# EuroOwl.net
KiCad netlist of a schematic drawn in EAGLE
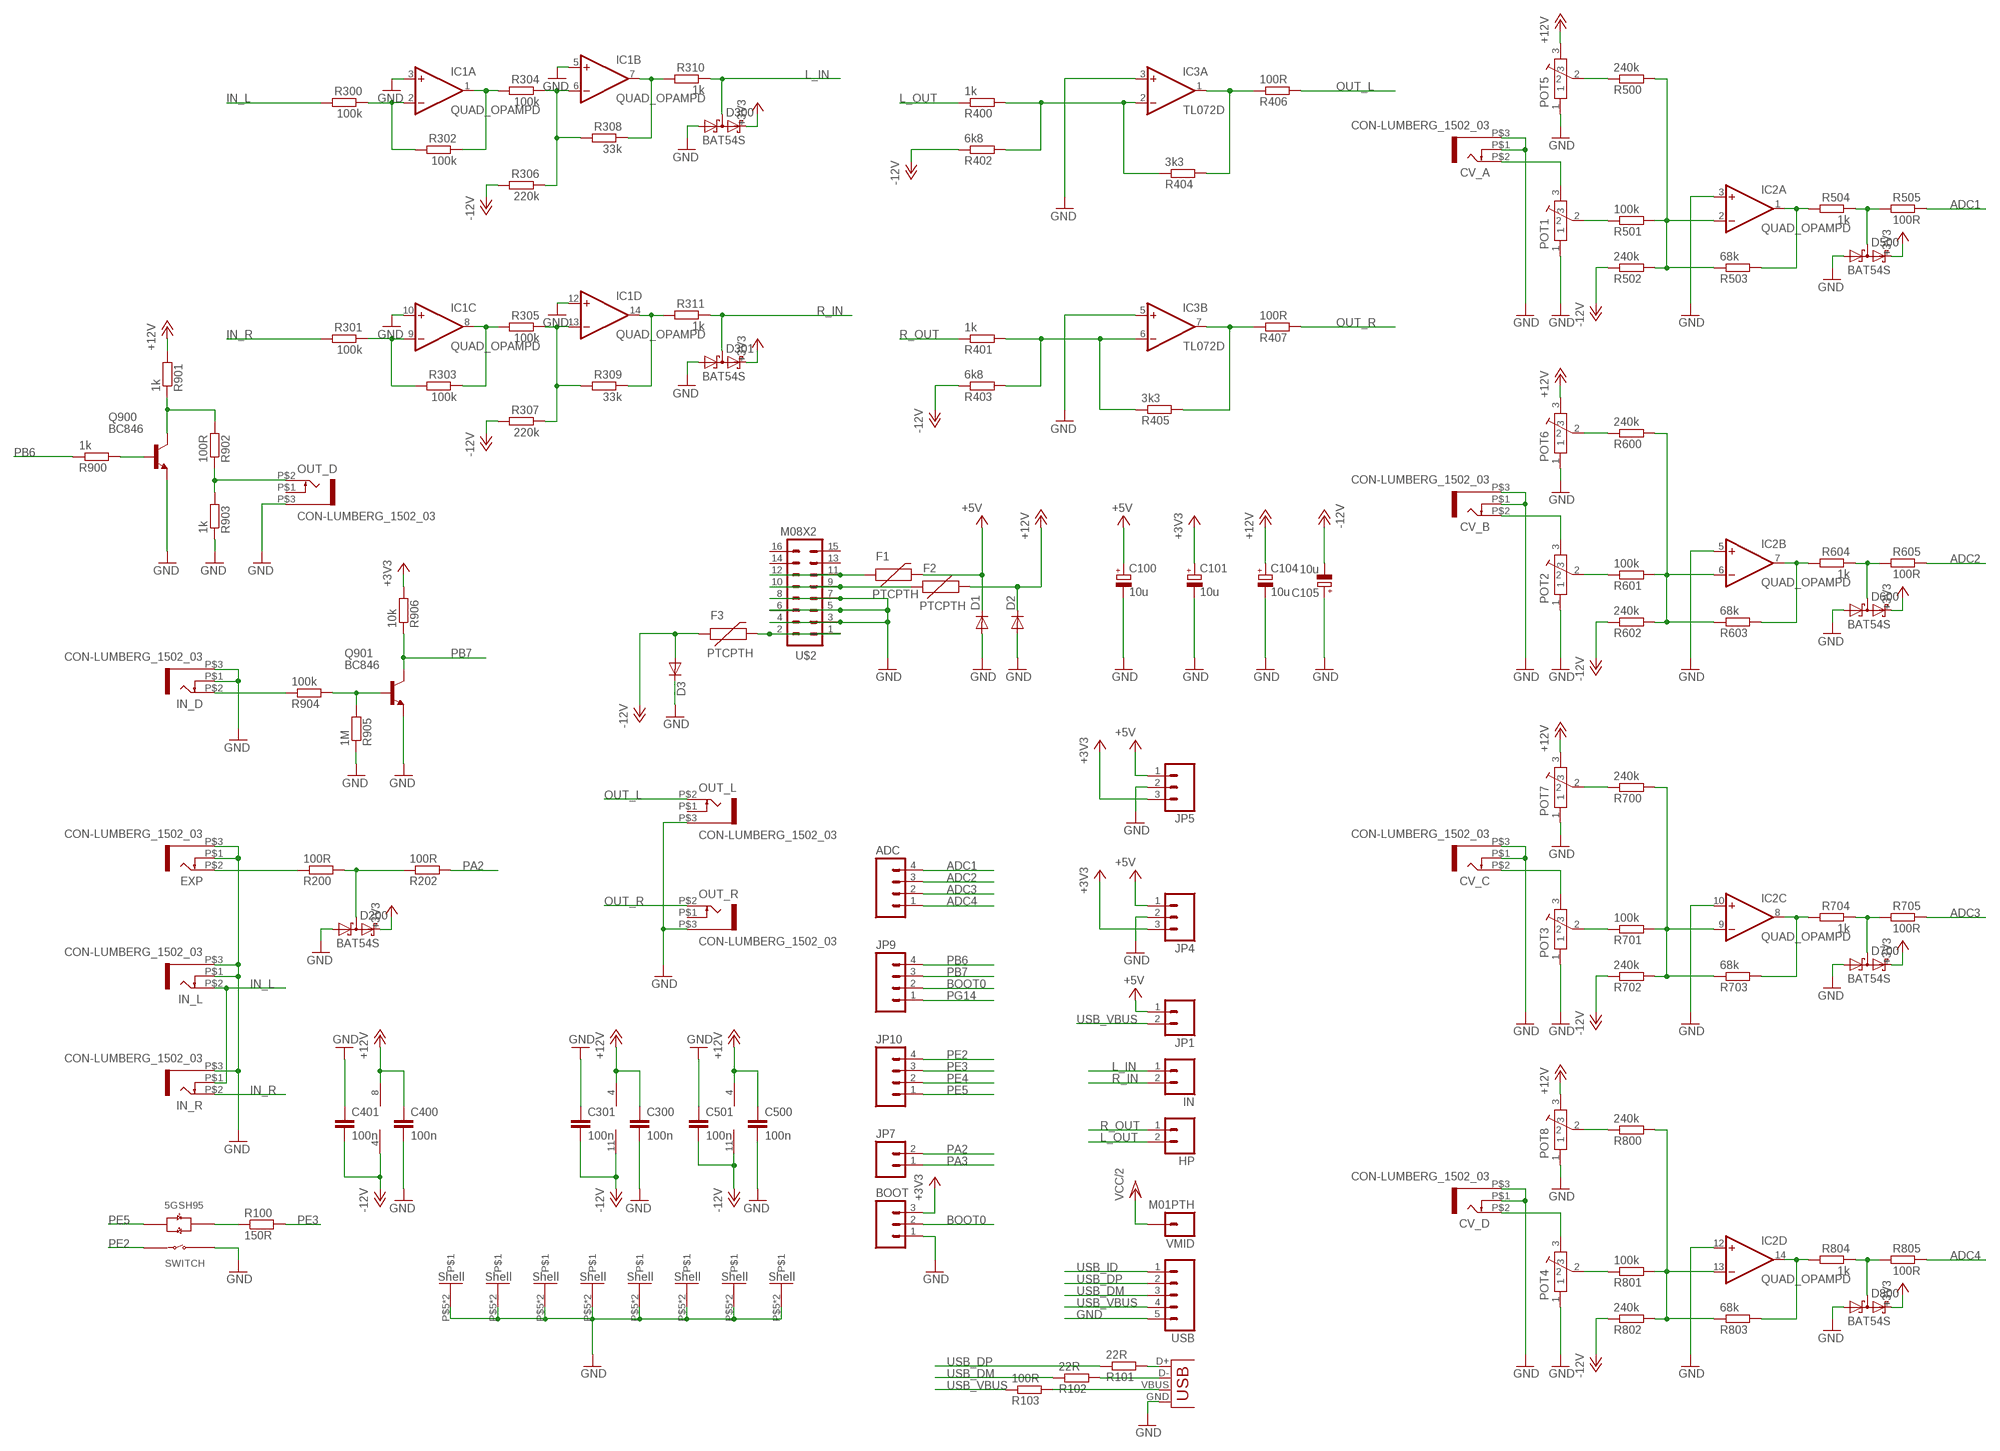
[diagram p0: schematic, sheet 1]

(export (version "E")
  (design (tool "Eeschema 10.0.6"))
  (components
    (comp (ref "ADC")
      (value "M04PTH")
      (footprint "eagle-import:1X04")
      (libsource (lib "eagle-import") (part "M04PTH"))
    )
    (comp (ref "BOOT")
      (value "M03PTH")
      (footprint "eagle-import:1X03")
      (libsource (lib "eagle-import") (part "M03PTH"))
    )
    (comp (ref "C100")
      (value "10u")
      (footprint "eagle-import:PANASONIC_A")
      (libsource (lib "eagle-import") (part "CPOL-EUA"))
    )
    (comp (ref "C101")
      (value "10u")
      (footprint "eagle-import:PANASONIC_A")
      (libsource (lib "eagle-import") (part "CPOL-EUA"))
    )
    (comp (ref "C104")
      (value "10u")
      (footprint "eagle-import:PANASONIC_A")
      (libsource (lib "eagle-import") (part "CPOL-EUA"))
    )
    (comp (ref "C105")
      (value "10u")
      (footprint "eagle-import:PANASONIC_A")
      (libsource (lib "eagle-import") (part "CPOL-EUA"))
    )
    (comp (ref "C300")
      (value "100n")
      (footprint "eagle-import:C0603")
      (libsource (lib "eagle-import") (part "C-EUC0603"))
    )
    (comp (ref "C301")
      (value "100n")
      (footprint "eagle-import:C0603")
      (libsource (lib "eagle-import") (part "C-EUC0603"))
    )
    (comp (ref "C400")
      (value "100n")
      (footprint "eagle-import:C0603")
      (libsource (lib "eagle-import") (part "C-EUC0603"))
    )
    (comp (ref "C401")
      (value "100n")
      (footprint "eagle-import:C0603")
      (libsource (lib "eagle-import") (part "C-EUC0603"))
    )
    (comp (ref "C500")
      (value "100n")
      (footprint "eagle-import:C0603")
      (libsource (lib "eagle-import") (part "C-EUC0603"))
    )
    (comp (ref "C501")
      (value "100n")
      (footprint "eagle-import:C0603")
      (libsource (lib "eagle-import") (part "C-EUC0603"))
    )
    (comp (ref "CV_A")
      (value "CON-LUMBERG_1502_03")
      (footprint "eagle-import:CON-LUMBERG_1502_03")
      (libsource (lib "eagle-import") (part "CON-LUMBERG_1502_03"))
    )
    (comp (ref "CV_B")
      (value "CON-LUMBERG_1502_03")
      (footprint "eagle-import:CON-LUMBERG_1502_03")
      (libsource (lib "eagle-import") (part "CON-LUMBERG_1502_03"))
    )
    (comp (ref "CV_C")
      (value "CON-LUMBERG_1502_03")
      (footprint "eagle-import:CON-LUMBERG_1502_03")
      (libsource (lib "eagle-import") (part "CON-LUMBERG_1502_03"))
    )
    (comp (ref "CV_D")
      (value "CON-LUMBERG_1502_03")
      (footprint "eagle-import:CON-LUMBERG_1502_03")
      (libsource (lib "eagle-import") (part "CON-LUMBERG_1502_03"))
    )
    (comp (ref "D1")
      (value "DIODE1N4001")
      (footprint "eagle-import:DIODE-1N4001")
      (libsource (lib "eagle-import") (part "DIODE1N4001"))
    )
    (comp (ref "D2")
      (value "DIODE1N4001")
      (footprint "eagle-import:DIODE-1N4001")
      (libsource (lib "eagle-import") (part "DIODE1N4001"))
    )
    (comp (ref "D3")
      (value "DIODE1N4001")
      (footprint "eagle-import:DIODE-1N4001")
      (libsource (lib "eagle-import") (part "DIODE1N4001"))
    )
    (comp (ref "D200")
      (value "BAT54S")
      (footprint "eagle-import:SOT23")
      (libsource (lib "eagle-import") (part "BAT54S"))
    )
    (comp (ref "D300")
      (value "BAT54S")
      (footprint "eagle-import:SOT23")
      (libsource (lib "eagle-import") (part "BAT54S"))
    )
    (comp (ref "D301")
      (value "BAT54S")
      (footprint "eagle-import:SOT23")
      (libsource (lib "eagle-import") (part "BAT54S"))
    )
    (comp (ref "D500")
      (value "BAT54S")
      (footprint "eagle-import:SOT23")
      (libsource (lib "eagle-import") (part "BAT54S"))
    )
    (comp (ref "D600")
      (value "BAT54S")
      (footprint "eagle-import:SOT23")
      (libsource (lib "eagle-import") (part "BAT54S"))
    )
    (comp (ref "D700")
      (value "BAT54S")
      (footprint "eagle-import:SOT23")
      (libsource (lib "eagle-import") (part "BAT54S"))
    )
    (comp (ref "D800")
      (value "BAT54S")
      (footprint "eagle-import:SOT23")
      (libsource (lib "eagle-import") (part "BAT54S"))
    )
    (comp (ref "EXP")
      (value "CON-LUMBERG_1502_03")
      (footprint "eagle-import:CON-LUMBERG_1502_03")
      (libsource (lib "eagle-import") (part "CON-LUMBERG_1502_03"))
    )
    (comp (ref "F1")
      (value "PTCPTH")
      (footprint "eagle-import:PTC")
      (libsource (lib "eagle-import") (part "PTCPTH"))
    )
    (comp (ref "F2")
      (value "PTCPTH")
      (footprint "eagle-import:PTC")
      (libsource (lib "eagle-import") (part "PTCPTH"))
    )
    (comp (ref "F3")
      (value "PTCPTH")
      (footprint "eagle-import:PTC")
      (libsource (lib "eagle-import") (part "PTCPTH"))
    )
    (comp (ref "HP")
      (value "M02PTH")
      (footprint "eagle-import:1X02")
      (libsource (lib "eagle-import") (part "M02PTH"))
    )
    (comp (ref "IC1")
      (value "QUAD_OPAMPD")
      (footprint "eagle-import:SO14")
      (libsource (lib "eagle-import") (part "QUAD_OPAMPD"))
    )
    (comp (ref "IC2")
      (value "QUAD_OPAMPD")
      (footprint "eagle-import:SO14")
      (libsource (lib "eagle-import") (part "QUAD_OPAMPD"))
    )
    (comp (ref "IC3")
      (value "TL072D")
      (footprint "eagle-import:SO08")
      (libsource (lib "eagle-import") (part "TL072D"))
    )
    (comp (ref "IN")
      (value "M02PTH")
      (footprint "eagle-import:1X02")
      (libsource (lib "eagle-import") (part "M02PTH"))
    )
    (comp (ref "IN_D")
      (value "CON-LUMBERG_1502_03")
      (footprint "eagle-import:CON-LUMBERG_1502_03")
      (libsource (lib "eagle-import") (part "CON-LUMBERG_1502_03"))
    )
    (comp (ref "IN_L")
      (value "CON-LUMBERG_1502_03")
      (footprint "eagle-import:CON-LUMBERG_1502_03")
      (libsource (lib "eagle-import") (part "CON-LUMBERG_1502_03"))
    )
    (comp (ref "IN_R")
      (value "CON-LUMBERG_1502_03")
      (footprint "eagle-import:CON-LUMBERG_1502_03")
      (libsource (lib "eagle-import") (part "CON-LUMBERG_1502_03"))
    )
    (comp (ref "JP1")
      (value "M02PTH")
      (footprint "eagle-import:1X02")
      (libsource (lib "eagle-import") (part "M02PTH"))
    )
    (comp (ref "JP4")
      (value "M03PTH")
      (footprint "eagle-import:1X03")
      (libsource (lib "eagle-import") (part "M03PTH"))
    )
    (comp (ref "JP5")
      (value "M03PTH")
      (footprint "eagle-import:1X03")
      (libsource (lib "eagle-import") (part "M03PTH"))
    )
    (comp (ref "JP7")
      (value "M02PTH")
      (footprint "eagle-import:1X02")
      (libsource (lib "eagle-import") (part "M02PTH"))
    )
    (comp (ref "JP9")
      (value "M04PTH")
      (footprint "eagle-import:1X04")
      (libsource (lib "eagle-import") (part "M04PTH"))
    )
    (comp (ref "JP10")
      (value "M04PTH")
      (footprint "eagle-import:1X04")
      (libsource (lib "eagle-import") (part "M04PTH"))
    )
    (comp (ref "OUT_D")
      (value "CON-LUMBERG_1502_03")
      (footprint "eagle-import:CON-LUMBERG_1502_03")
      (libsource (lib "eagle-import") (part "CON-LUMBERG_1502_03"))
    )
    (comp (ref "OUT_L")
      (value "CON-LUMBERG_1502_03")
      (footprint "eagle-import:CON-LUMBERG_1502_03")
      (libsource (lib "eagle-import") (part "CON-LUMBERG_1502_03"))
    )
    (comp (ref "OUT_R")
      (value "CON-LUMBERG_1502_03")
      (footprint "eagle-import:CON-LUMBERG_1502_03")
      (libsource (lib "eagle-import") (part "CON-LUMBERG_1502_03"))
    )
    (comp (ref "POT1")
      (value "POT-ALPS-RK09L1140")
      (footprint "eagle-import:POT-ALPS-RK09L1140")
      (libsource (lib "eagle-import") (part "POT-ALPS-RK09L1140"))
    )
    (comp (ref "POT2")
      (value "POT-ALPS-RK09L1140")
      (footprint "eagle-import:POT-ALPS-RK09L1140")
      (libsource (lib "eagle-import") (part "POT-ALPS-RK09L1140"))
    )
    (comp (ref "POT3")
      (value "POT-ALPS-RK09L1140")
      (footprint "eagle-import:POT-ALPS-RK09L1140")
      (libsource (lib "eagle-import") (part "POT-ALPS-RK09L1140"))
    )
    (comp (ref "POT4")
      (value "POT-ALPS-RK09L1140")
      (footprint "eagle-import:POT-ALPS-RK09L1140")
      (libsource (lib "eagle-import") (part "POT-ALPS-RK09L1140"))
    )
    (comp (ref "POT5")
      (value "POT-ALPS-RK09L1140")
      (footprint "eagle-import:POT-ALPS-RK09L1140")
      (libsource (lib "eagle-import") (part "POT-ALPS-RK09L1140"))
    )
    (comp (ref "POT6")
      (value "POT-ALPS-RK09L1140")
      (footprint "eagle-import:POT-ALPS-RK09L1140")
      (libsource (lib "eagle-import") (part "POT-ALPS-RK09L1140"))
    )
    (comp (ref "POT7")
      (value "POT-ALPS-RK09L1140")
      (footprint "eagle-import:POT-ALPS-RK09L1140")
      (libsource (lib "eagle-import") (part "POT-ALPS-RK09L1140"))
    )
    (comp (ref "POT8")
      (value "POT-ALPS-RK09L1140")
      (footprint "eagle-import:POT-ALPS-RK09L1140")
      (libsource (lib "eagle-import") (part "POT-ALPS-RK09L1140"))
    )
    (comp (ref "Q900")
      (value "BC846")
      (footprint "eagle-import:SOT23")
      (libsource (lib "eagle-import") (part "BC846"))
    )
    (comp (ref "Q901")
      (value "BC846")
      (footprint "eagle-import:SOT23")
      (libsource (lib "eagle-import") (part "BC846"))
    )
    (comp (ref "R100")
      (value "150R")
      (footprint "eagle-import:0603")
      (libsource (lib "eagle-import") (part "R-EU_0603"))
    )
    (comp (ref "R101")
      (value "22R")
      (footprint "eagle-import:0603")
      (libsource (lib "eagle-import") (part "R-EU_0603"))
    )
    (comp (ref "R102")
      (value "22R")
      (footprint "eagle-import:0603")
      (libsource (lib "eagle-import") (part "R-EU_0603"))
    )
    (comp (ref "R103")
      (value "100R")
      (footprint "eagle-import:0603")
      (libsource (lib "eagle-import") (part "R-EU_0603"))
    )
    (comp (ref "R200")
      (value "100R")
      (footprint "eagle-import:0603")
      (libsource (lib "eagle-import") (part "R-EU_0603"))
    )
    (comp (ref "R202")
      (value "100R")
      (footprint "eagle-import:0603")
      (libsource (lib "eagle-import") (part "R-EU_0603"))
    )
    (comp (ref "R300")
      (value "100k")
      (footprint "eagle-import:0603")
      (libsource (lib "eagle-import") (part "R-EU_0603"))
    )
    (comp (ref "R301")
      (value "100k")
      (footprint "eagle-import:0603")
      (libsource (lib "eagle-import") (part "R-EU_0603"))
    )
    (comp (ref "R302")
      (value "100k")
      (footprint "eagle-import:0603")
      (libsource (lib "eagle-import") (part "R-EU_0603"))
    )
    (comp (ref "R303")
      (value "100k")
      (footprint "eagle-import:0603")
      (libsource (lib "eagle-import") (part "R-EU_0603"))
    )
    (comp (ref "R304")
      (value "100k")
      (footprint "eagle-import:0603")
      (libsource (lib "eagle-import") (part "R-EU_0603"))
    )
    (comp (ref "R305")
      (value "100k")
      (footprint "eagle-import:0603")
      (libsource (lib "eagle-import") (part "R-EU_0603"))
    )
    (comp (ref "R306")
      (value "220k")
      (footprint "eagle-import:0603")
      (libsource (lib "eagle-import") (part "R-EU_0603"))
    )
    (comp (ref "R307")
      (value "220k")
      (footprint "eagle-import:0603")
      (libsource (lib "eagle-import") (part "R-EU_0603"))
    )
    (comp (ref "R308")
      (value "33k")
      (footprint "eagle-import:0603")
      (libsource (lib "eagle-import") (part "R-EU_0603"))
    )
    (comp (ref "R309")
      (value "33k")
      (footprint "eagle-import:0603")
      (libsource (lib "eagle-import") (part "R-EU_0603"))
    )
    (comp (ref "R310")
      (value "1k")
      (footprint "eagle-import:0603")
      (libsource (lib "eagle-import") (part "R-EU_0603"))
    )
    (comp (ref "R311")
      (value "1k")
      (footprint "eagle-import:0603")
      (libsource (lib "eagle-import") (part "R-EU_0603"))
    )
    (comp (ref "R400")
      (value "1k")
      (footprint "eagle-import:0603")
      (libsource (lib "eagle-import") (part "R-EU_0603"))
    )
    (comp (ref "R401")
      (value "1k")
      (footprint "eagle-import:0603")
      (libsource (lib "eagle-import") (part "R-EU_0603"))
    )
    (comp (ref "R402")
      (value "6k8")
      (footprint "eagle-import:0603")
      (libsource (lib "eagle-import") (part "R-EU_0603"))
    )
    (comp (ref "R403")
      (value "6k8")
      (footprint "eagle-import:0603")
      (libsource (lib "eagle-import") (part "R-EU_0603"))
    )
    (comp (ref "R404")
      (value "3k3")
      (footprint "eagle-import:0603")
      (libsource (lib "eagle-import") (part "R-EU_0603"))
    )
    (comp (ref "R405")
      (value "3k3")
      (footprint "eagle-import:0603")
      (libsource (lib "eagle-import") (part "R-EU_0603"))
    )
    (comp (ref "R406")
      (value "100R")
      (footprint "eagle-import:0603")
      (libsource (lib "eagle-import") (part "R-EU_0603"))
    )
    (comp (ref "R407")
      (value "100R")
      (footprint "eagle-import:0603")
      (libsource (lib "eagle-import") (part "R-EU_0603"))
    )
    (comp (ref "R500")
      (value "240k")
      (footprint "eagle-import:0603")
      (libsource (lib "eagle-import") (part "R-EU_0603"))
    )
    (comp (ref "R501")
      (value "100k")
      (footprint "eagle-import:0603")
      (libsource (lib "eagle-import") (part "R-EU_0603"))
    )
    (comp (ref "R502")
      (value "240k")
      (footprint "eagle-import:0603")
      (libsource (lib "eagle-import") (part "R-EU_0603"))
    )
    (comp (ref "R503")
      (value "68k")
      (footprint "eagle-import:0603")
      (libsource (lib "eagle-import") (part "R-EU_0603"))
    )
    (comp (ref "R504")
      (value "1k")
      (footprint "eagle-import:0603")
      (libsource (lib "eagle-import") (part "R-EU_0603"))
    )
    (comp (ref "R505")
      (value "100R")
      (footprint "eagle-import:0603")
      (libsource (lib "eagle-import") (part "R-EU_0603"))
    )
    (comp (ref "R600")
      (value "240k")
      (footprint "eagle-import:0603")
      (libsource (lib "eagle-import") (part "R-EU_0603"))
    )
    (comp (ref "R601")
      (value "100k")
      (footprint "eagle-import:0603")
      (libsource (lib "eagle-import") (part "R-EU_0603"))
    )
    (comp (ref "R602")
      (value "240k")
      (footprint "eagle-import:0603")
      (libsource (lib "eagle-import") (part "R-EU_0603"))
    )
    (comp (ref "R603")
      (value "68k")
      (footprint "eagle-import:0603")
      (libsource (lib "eagle-import") (part "R-EU_0603"))
    )
    (comp (ref "R604")
      (value "1k")
      (footprint "eagle-import:0603")
      (libsource (lib "eagle-import") (part "R-EU_0603"))
    )
    (comp (ref "R605")
      (value "100R")
      (footprint "eagle-import:0603")
      (libsource (lib "eagle-import") (part "R-EU_0603"))
    )
    (comp (ref "R700")
      (value "240k")
      (footprint "eagle-import:0603")
      (libsource (lib "eagle-import") (part "R-EU_0603"))
    )
    (comp (ref "R701")
      (value "100k")
      (footprint "eagle-import:0603")
      (libsource (lib "eagle-import") (part "R-EU_0603"))
    )
    (comp (ref "R702")
      (value "240k")
      (footprint "eagle-import:0603")
      (libsource (lib "eagle-import") (part "R-EU_0603"))
    )
    (comp (ref "R703")
      (value "68k")
      (footprint "eagle-import:0603")
      (libsource (lib "eagle-import") (part "R-EU_0603"))
    )
    (comp (ref "R704")
      (value "1k")
      (footprint "eagle-import:0603")
      (libsource (lib "eagle-import") (part "R-EU_0603"))
    )
    (comp (ref "R705")
      (value "100R")
      (footprint "eagle-import:0603")
      (libsource (lib "eagle-import") (part "R-EU_0603"))
    )
    (comp (ref "R800")
      (value "240k")
      (footprint "eagle-import:0603")
      (libsource (lib "eagle-import") (part "R-EU_0603"))
    )
    (comp (ref "R801")
      (value "100k")
      (footprint "eagle-import:0603")
      (libsource (lib "eagle-import") (part "R-EU_0603"))
    )
    (comp (ref "R802")
      (value "240k")
      (footprint "eagle-import:0603")
      (libsource (lib "eagle-import") (part "R-EU_0603"))
    )
    (comp (ref "R803")
      (value "68k")
      (footprint "eagle-import:0603")
      (libsource (lib "eagle-import") (part "R-EU_0603"))
    )
    (comp (ref "R804")
      (value "1k")
      (footprint "eagle-import:0603")
      (libsource (lib "eagle-import") (part "R-EU_0603"))
    )
    (comp (ref "R805")
      (value "100R")
      (footprint "eagle-import:0603")
      (libsource (lib "eagle-import") (part "R-EU_0603"))
    )
    (comp (ref "R900")
      (value "1k")
      (footprint "eagle-import:0603")
      (libsource (lib "eagle-import") (part "R-EU_0603"))
    )
    (comp (ref "R901")
      (value "1k")
      (footprint "eagle-import:0603")
      (libsource (lib "eagle-import") (part "R-EU_0603"))
    )
    (comp (ref "R902")
      (value "100R")
      (footprint "eagle-import:0603")
      (libsource (lib "eagle-import") (part "R-EU_0603"))
    )
    (comp (ref "R903")
      (value "1k")
      (footprint "eagle-import:0603")
      (libsource (lib "eagle-import") (part "R-EU_0603"))
    )
    (comp (ref "R904")
      (value "100k")
      (footprint "eagle-import:0603")
      (libsource (lib "eagle-import") (part "R-EU_0603"))
    )
    (comp (ref "R905")
      (value "1M")
      (footprint "eagle-import:0603")
      (libsource (lib "eagle-import") (part "R-EU_0603"))
    )
    (comp (ref "R906")
      (value "10k")
      (footprint "eagle-import:0603")
      (libsource (lib "eagle-import") (part "R-EU_0603"))
    )
    (comp (ref "U$1")
      (value "5GTH9")
      (footprint "eagle-import:5GTH9")
      (libsource (lib "eagle-import") (part "5GTH9"))
    )
    (comp (ref "U$2")
      (value "M08X2")
      (footprint "eagle-import:2X8")
      (libsource (lib "eagle-import") (part "M08X2"))
    )
    (comp (ref "USB")
      (value "M05PTH")
      (footprint "eagle-import:1X05")
      (libsource (lib "eagle-import") (part "M05PTH"))
    )
    (comp (ref "VMID")
      (value "M01PTH")
      (footprint "eagle-import:1X01")
      (libsource (lib "eagle-import") (part "M01PTH"))
    )
    (comp (ref "X1")
      (value "USBPTH-VERTICAL")
      (footprint "eagle-import:USB-B-PTH-VERTICAL")
      (libsource (lib "eagle-import") (part "USBPTH-VERTICAL"))
    )
  )
  (nets
    (net (code "1") (name "+3V3") (class "Default")
      (node (ref "BOOT") (pin "3") (pinfunction "3_3") (pintype "passive"))
      (node (ref "C101") (pin "+") (pinfunction "+_+") (pintype "passive"))
      (node (ref "D200") (pin "2") (pinfunction "C2_2") (pintype "passive"))
      (node (ref "D300") (pin "2") (pinfunction "C2_2") (pintype "passive"))
      (node (ref "D301") (pin "2") (pinfunction "C2_2") (pintype "passive"))
      (node (ref "D500") (pin "2") (pinfunction "C2_2") (pintype "passive"))
      (node (ref "D600") (pin "2") (pinfunction "C2_2") (pintype "passive"))
      (node (ref "D700") (pin "2") (pinfunction "C2_2") (pintype "passive"))
      (node (ref "D800") (pin "2") (pinfunction "C2_2") (pintype "passive"))
      (node (ref "JP4") (pin "3") (pinfunction "3_3") (pintype "passive"))
      (node (ref "JP5") (pin "3") (pinfunction "3_3") (pintype "passive"))
      (node (ref "R906") (pin "2") (pinfunction "2_2") (pintype "passive"))
    )
    (net (code "2") (name "+5V") (class "Default")
      (node (ref "C100") (pin "+") (pinfunction "+_+") (pintype "passive"))
      (node (ref "D1") (pin "C") (pinfunction "C_C") (pintype "passive"))
      (node (ref "F1") (pin "P$2") (pinfunction "2_P$2") (pintype "bidirectional"))
      (node (ref "JP1") (pin "1") (pinfunction "1_1") (pintype "passive"))
      (node (ref "JP4") (pin "1") (pinfunction "1_1") (pintype "passive"))
      (node (ref "JP5") (pin "1") (pinfunction "1_1") (pintype "passive"))
    )
    (net (code "3") (name "+12V") (class "Default")
      (node (ref "C104") (pin "+") (pinfunction "+_+") (pintype "passive"))
      (node (ref "C300") (pin "1") (pinfunction "1_1") (pintype "passive"))
      (node (ref "C400") (pin "1") (pinfunction "1_1") (pintype "passive"))
      (node (ref "C500") (pin "1") (pinfunction "1_1") (pintype "passive"))
      (node (ref "D2") (pin "C") (pinfunction "C_C") (pintype "passive"))
      (node (ref "F2") (pin "P$2") (pinfunction "2_P$2") (pintype "bidirectional"))
      (node (ref "IC1") (pin "4") (pinfunction "V+_4") (pintype "power_in"))
      (node (ref "IC2") (pin "4") (pinfunction "V+_4") (pintype "power_in"))
      (node (ref "IC3") (pin "8") (pinfunction "V+_8") (pintype "power_in"))
      (node (ref "POT5") (pin "3") (pinfunction "3_3") (pintype "bidirectional"))
      (node (ref "POT6") (pin "3") (pinfunction "3_3") (pintype "bidirectional"))
      (node (ref "POT7") (pin "3") (pinfunction "3_3") (pintype "bidirectional"))
      (node (ref "POT8") (pin "3") (pinfunction "3_3") (pintype "bidirectional"))
      (node (ref "R901") (pin "2") (pinfunction "2_2") (pintype "passive"))
    )
    (net (code "4") (name "-12V") (class "Default")
      (node (ref "C105") (pin "-") (pinfunction "-_-") (pintype "passive"))
      (node (ref "C301") (pin "2") (pinfunction "2_2") (pintype "passive"))
      (node (ref "C401") (pin "2") (pinfunction "2_2") (pintype "passive"))
      (node (ref "C501") (pin "2") (pinfunction "2_2") (pintype "passive"))
      (node (ref "D3") (pin "A") (pinfunction "A_A") (pintype "passive"))
      (node (ref "F3") (pin "P$1") (pinfunction "1_P$1") (pintype "bidirectional"))
      (node (ref "IC1") (pin "11") (pinfunction "V-_11") (pintype "power_in"))
      (node (ref "IC2") (pin "11") (pinfunction "V-_11") (pintype "power_in"))
      (node (ref "IC3") (pin "4") (pinfunction "V-_4") (pintype "power_in"))
      (node (ref "R306") (pin "2") (pinfunction "2_2") (pintype "passive"))
      (node (ref "R307") (pin "2") (pinfunction "2_2") (pintype "passive"))
      (node (ref "R402") (pin "1") (pinfunction "1_1") (pintype "passive"))
      (node (ref "R403") (pin "1") (pinfunction "1_1") (pintype "passive"))
      (node (ref "R502") (pin "1") (pinfunction "1_1") (pintype "passive"))
      (node (ref "R602") (pin "1") (pinfunction "1_1") (pintype "passive"))
      (node (ref "R702") (pin "1") (pinfunction "1_1") (pintype "passive"))
      (node (ref "R802") (pin "1") (pinfunction "1_1") (pintype "passive"))
    )
    (net (code "5") (name "/ADC1") (class "Default")
      (node (ref "ADC") (pin "4") (pinfunction "4_4") (pintype "passive"))
      (node (ref "R505") (pin "1") (pinfunction "1_1") (pintype "passive"))
    )
    (net (code "6") (name "/ADC2") (class "Default")
      (node (ref "ADC") (pin "3") (pinfunction "3_3") (pintype "passive"))
      (node (ref "R605") (pin "1") (pinfunction "1_1") (pintype "passive"))
    )
    (net (code "7") (name "/ADC3") (class "Default")
      (node (ref "ADC") (pin "2") (pinfunction "2_2") (pintype "passive"))
      (node (ref "R705") (pin "1") (pinfunction "1_1") (pintype "passive"))
    )
    (net (code "8") (name "/ADC4") (class "Default")
      (node (ref "ADC") (pin "1") (pinfunction "1_1") (pintype "passive"))
      (node (ref "R805") (pin "1") (pinfunction "1_1") (pintype "passive"))
    )
    (net (code "9") (name "/BOOT0") (class "Default")
      (node (ref "BOOT") (pin "2") (pinfunction "2_2") (pintype "passive"))
      (node (ref "JP9") (pin "2") (pinfunction "2_2") (pintype "passive"))
    )
    (net (code "10") (name "/IN_L") (class "Default")
      (node (ref "IN_L") (pin "P$2") (pinfunction "3_P$2") (pintype "passive"))
      (node (ref "IN_R") (pin "P$1") (pinfunction "4_P$1") (pintype "passive"))
      (node (ref "R300") (pin "2") (pinfunction "2_2") (pintype "passive"))
    )
    (net (code "11") (name "/IN_R") (class "Default")
      (node (ref "IN_R") (pin "P$2") (pinfunction "3_P$2") (pintype "passive"))
      (node (ref "R301") (pin "2") (pinfunction "2_2") (pintype "passive"))
    )
    (net (code "12") (name "/L_IN") (class "Default")
      (node (ref "D300") (pin "3") (pinfunction "C1A2_3") (pintype "passive"))
      (node (ref "IN") (pin "1") (pinfunction "1_1") (pintype "passive"))
      (node (ref "R310") (pin "1") (pinfunction "1_1") (pintype "passive"))
    )
    (net (code "13") (name "/L_OUT") (class "Default")
      (node (ref "HP") (pin "2") (pinfunction "2_2") (pintype "passive"))
      (node (ref "R400") (pin "1") (pinfunction "1_1") (pintype "passive"))
    )
    (net (code "14") (name "/OUT_L") (class "Default")
      (node (ref "OUT_L") (pin "P$2") (pinfunction "3_P$2") (pintype "passive"))
      (node (ref "R406") (pin "2") (pinfunction "2_2") (pintype "passive"))
    )
    (net (code "15") (name "/OUT_R") (class "Default")
      (node (ref "OUT_R") (pin "P$2") (pinfunction "3_P$2") (pintype "passive"))
      (node (ref "R407") (pin "2") (pinfunction "2_2") (pintype "passive"))
    )
    (net (code "16") (name "/PA2") (class "Default")
      (node (ref "JP7") (pin "2") (pinfunction "2_2") (pintype "passive"))
      (node (ref "R202") (pin "2") (pinfunction "2_2") (pintype "passive"))
    )
    (net (code "17") (name "/PA3") (class "Default")
      (node (ref "JP7") (pin "1") (pinfunction "1_1") (pintype "passive"))
    )
    (net (code "18") (name "/PB6") (class "Default")
      (node (ref "JP9") (pin "4") (pinfunction "4_4") (pintype "passive"))
      (node (ref "R900") (pin "1") (pinfunction "1_1") (pintype "passive"))
    )
    (net (code "19") (name "/PB7") (class "Default")
      (node (ref "JP9") (pin "3") (pinfunction "3_3") (pintype "passive"))
      (node (ref "Q901") (pin "3") (pinfunction "C_3") (pintype "passive"))
      (node (ref "R906") (pin "1") (pinfunction "1_1") (pintype "passive"))
    )
    (net (code "20") (name "/PE2") (class "Default")
      (node (ref "JP10") (pin "4") (pinfunction "4_4") (pintype "passive"))
      (node (ref "U$1") (pin "4") (pinfunction "SWITCH_A_4") (pintype "power_in"))
    )
    (net (code "21") (name "/PE3") (class "Default")
      (node (ref "JP10") (pin "3") (pinfunction "3_3") (pintype "passive"))
      (node (ref "R100") (pin "2") (pinfunction "2_2") (pintype "passive"))
    )
    (net (code "22") (name "/PE4") (class "Default")
      (node (ref "JP10") (pin "2") (pinfunction "2_2") (pintype "passive"))
    )
    (net (code "23") (name "/PE5") (class "Default")
      (node (ref "JP10") (pin "1") (pinfunction "1_1") (pintype "passive"))
      (node (ref "U$1") (pin "-2") (pinfunction "LED_G+_-2") (pintype "input"))
    )
    (net (code "24") (name "/PG14") (class "Default")
      (node (ref "JP9") (pin "1") (pinfunction "1_1") (pintype "passive"))
    )
    (net (code "25") (name "/R_IN") (class "Default")
      (node (ref "D301") (pin "3") (pinfunction "C1A2_3") (pintype "passive"))
      (node (ref "IN") (pin "2") (pinfunction "2_2") (pintype "passive"))
      (node (ref "R311") (pin "1") (pinfunction "1_1") (pintype "passive"))
    )
    (net (code "26") (name "/R_OUT") (class "Default")
      (node (ref "HP") (pin "1") (pinfunction "1_1") (pintype "passive"))
      (node (ref "R401") (pin "1") (pinfunction "1_1") (pintype "passive"))
    )
    (net (code "27") (name "/USB_DM") (class "Default")
      (node (ref "R102") (pin "1") (pinfunction "1_1") (pintype "passive"))
      (node (ref "USB") (pin "3") (pinfunction "3_3") (pintype "passive"))
    )
    (net (code "28") (name "/USB_DP") (class "Default")
      (node (ref "R101") (pin "1") (pinfunction "1_1") (pintype "passive"))
      (node (ref "USB") (pin "2") (pinfunction "2_2") (pintype "passive"))
    )
    (net (code "29") (name "/USB_ID") (class "Default")
      (node (ref "USB") (pin "1") (pinfunction "1_1") (pintype "passive"))
    )
    (net (code "30") (name "/USB_VBUS") (class "Default")
      (node (ref "JP1") (pin "2") (pinfunction "2_2") (pintype "passive"))
      (node (ref "R103") (pin "1") (pinfunction "1_1") (pintype "passive"))
      (node (ref "USB") (pin "4") (pinfunction "4_4") (pintype "passive"))
    )
    (net (code "31") (name "GND") (class "Default")
      (node (ref "BOOT") (pin "1") (pinfunction "1_1") (pintype "passive"))
      (node (ref "C100") (pin "-") (pinfunction "-_-") (pintype "passive"))
      (node (ref "C101") (pin "-") (pinfunction "-_-") (pintype "passive"))
      (node (ref "C104") (pin "-") (pinfunction "-_-") (pintype "passive"))
      (node (ref "C105") (pin "+") (pinfunction "+_+") (pintype "passive"))
      (node (ref "C300") (pin "2") (pinfunction "2_2") (pintype "passive"))
      (node (ref "C301") (pin "1") (pinfunction "1_1") (pintype "passive"))
      (node (ref "C400") (pin "2") (pinfunction "2_2") (pintype "passive"))
      (node (ref "C401") (pin "1") (pinfunction "1_1") (pintype "passive"))
      (node (ref "C500") (pin "2") (pinfunction "2_2") (pintype "passive"))
      (node (ref "C501") (pin "1") (pinfunction "1_1") (pintype "passive"))
      (node (ref "CV_A") (pin "P$1") (pinfunction "4_P$1") (pintype "passive"))
      (node (ref "CV_A") (pin "P$3") (pinfunction "5_P$3") (pintype "passive"))
      (node (ref "CV_B") (pin "P$1") (pinfunction "4_P$1") (pintype "passive"))
      (node (ref "CV_B") (pin "P$3") (pinfunction "5_P$3") (pintype "passive"))
      (node (ref "CV_C") (pin "P$1") (pinfunction "4_P$1") (pintype "passive"))
      (node (ref "CV_C") (pin "P$3") (pinfunction "5_P$3") (pintype "passive"))
      (node (ref "CV_D") (pin "P$1") (pinfunction "4_P$1") (pintype "passive"))
      (node (ref "CV_D") (pin "P$3") (pinfunction "5_P$3") (pintype "passive"))
      (node (ref "D1") (pin "A") (pinfunction "A_A") (pintype "passive"))
      (node (ref "D2") (pin "A") (pinfunction "A_A") (pintype "passive"))
      (node (ref "D200") (pin "1") (pinfunction "A1_1") (pintype "passive"))
      (node (ref "D3") (pin "C") (pinfunction "C_C") (pintype "passive"))
      (node (ref "D300") (pin "1") (pinfunction "A1_1") (pintype "passive"))
      (node (ref "D301") (pin "1") (pinfunction "A1_1") (pintype "passive"))
      (node (ref "D500") (pin "1") (pinfunction "A1_1") (pintype "passive"))
      (node (ref "D600") (pin "1") (pinfunction "A1_1") (pintype "passive"))
      (node (ref "D700") (pin "1") (pinfunction "A1_1") (pintype "passive"))
      (node (ref "D800") (pin "1") (pinfunction "A1_1") (pintype "passive"))
      (node (ref "EXP") (pin "P$1") (pinfunction "4_P$1") (pintype "passive"))
      (node (ref "EXP") (pin "P$3") (pinfunction "5_P$3") (pintype "passive"))
      (node (ref "IC1") (pin "10") (pinfunction "+IN_10") (pintype "input"))
      (node (ref "IC1") (pin "12") (pinfunction "+IN_12") (pintype "input"))
      (node (ref "IC1") (pin "3") (pinfunction "+IN_3") (pintype "input"))
      (node (ref "IC1") (pin "5") (pinfunction "+IN_5") (pintype "input"))
      (node (ref "IC2") (pin "10") (pinfunction "+IN_10") (pintype "input"))
      (node (ref "IC2") (pin "12") (pinfunction "+IN_12") (pintype "input"))
      (node (ref "IC2") (pin "3") (pinfunction "+IN_3") (pintype "input"))
      (node (ref "IC2") (pin "5") (pinfunction "+IN_5") (pintype "input"))
      (node (ref "IC3") (pin "3") (pinfunction "+IN_3") (pintype "input"))
      (node (ref "IC3") (pin "5") (pinfunction "+IN_5") (pintype "input"))
      (node (ref "IN_D") (pin "P$1") (pinfunction "4_P$1") (pintype "passive"))
      (node (ref "IN_D") (pin "P$3") (pinfunction "5_P$3") (pintype "passive"))
      (node (ref "IN_L") (pin "P$1") (pinfunction "4_P$1") (pintype "passive"))
      (node (ref "IN_L") (pin "P$3") (pinfunction "5_P$3") (pintype "passive"))
      (node (ref "IN_R") (pin "P$3") (pinfunction "5_P$3") (pintype "passive"))
      (node (ref "JP4") (pin "2") (pinfunction "2_2") (pintype "passive"))
      (node (ref "JP5") (pin "2") (pinfunction "2_2") (pintype "passive"))
      (node (ref "OUT_D") (pin "P$3") (pinfunction "5_P$3") (pintype "passive"))
      (node (ref "OUT_L") (pin "P$3") (pinfunction "5_P$3") (pintype "passive"))
      (node (ref "OUT_R") (pin "P$3") (pinfunction "5_P$3") (pintype "passive"))
      (node (ref "POT1") (pin "1") (pinfunction "1_1") (pintype "bidirectional"))
      (node (ref "POT1") (pin "P$5") (pinfunction "P$1_P$5") (pintype "bidirectional"))
      (node (ref "POT1") (pin "P$6") (pinfunction "P$1_P$6") (pintype "bidirectional"))
      (node (ref "POT2") (pin "1") (pinfunction "1_1") (pintype "bidirectional"))
      (node (ref "POT2") (pin "P$5") (pinfunction "P$1_P$5") (pintype "bidirectional"))
      (node (ref "POT2") (pin "P$6") (pinfunction "P$1_P$6") (pintype "bidirectional"))
      (node (ref "POT3") (pin "1") (pinfunction "1_1") (pintype "bidirectional"))
      (node (ref "POT3") (pin "P$5") (pinfunction "P$1_P$5") (pintype "bidirectional"))
      (node (ref "POT3") (pin "P$6") (pinfunction "P$1_P$6") (pintype "bidirectional"))
      (node (ref "POT4") (pin "1") (pinfunction "1_1") (pintype "bidirectional"))
      (node (ref "POT4") (pin "P$5") (pinfunction "P$1_P$5") (pintype "bidirectional"))
      (node (ref "POT4") (pin "P$6") (pinfunction "P$1_P$6") (pintype "bidirectional"))
      (node (ref "POT5") (pin "1") (pinfunction "1_1") (pintype "bidirectional"))
      (node (ref "POT5") (pin "P$5") (pinfunction "P$1_P$5") (pintype "bidirectional"))
      (node (ref "POT5") (pin "P$6") (pinfunction "P$1_P$6") (pintype "bidirectional"))
      (node (ref "POT6") (pin "1") (pinfunction "1_1") (pintype "bidirectional"))
      (node (ref "POT6") (pin "P$5") (pinfunction "P$1_P$5") (pintype "bidirectional"))
      (node (ref "POT6") (pin "P$6") (pinfunction "P$1_P$6") (pintype "bidirectional"))
      (node (ref "POT7") (pin "1") (pinfunction "1_1") (pintype "bidirectional"))
      (node (ref "POT7") (pin "P$5") (pinfunction "P$1_P$5") (pintype "bidirectional"))
      (node (ref "POT7") (pin "P$6") (pinfunction "P$1_P$6") (pintype "bidirectional"))
      (node (ref "POT8") (pin "1") (pinfunction "1_1") (pintype "bidirectional"))
      (node (ref "POT8") (pin "P$5") (pinfunction "P$1_P$5") (pintype "bidirectional"))
      (node (ref "POT8") (pin "P$6") (pinfunction "P$1_P$6") (pintype "bidirectional"))
      (node (ref "Q900") (pin "2") (pinfunction "E_2") (pintype "passive"))
      (node (ref "Q901") (pin "2") (pinfunction "E_2") (pintype "passive"))
      (node (ref "R903") (pin "1") (pinfunction "1_1") (pintype "passive"))
      (node (ref "R905") (pin "1") (pinfunction "1_1") (pintype "passive"))
      (node (ref "U$1") (pin "1") (pinfunction "SWITCH_B_1") (pintype "power_in"))
      (node (ref "U$2") (pin "3") (pinfunction "3_3") (pintype "passive"))
      (node (ref "U$2") (pin "4") (pinfunction "4_4") (pintype "passive"))
      (node (ref "U$2") (pin "5") (pinfunction "5_5") (pintype "passive"))
      (node (ref "U$2") (pin "6") (pinfunction "6_6") (pintype "passive"))
      (node (ref "U$2") (pin "7") (pinfunction "7_7") (pintype "passive"))
      (node (ref "U$2") (pin "8") (pinfunction "8_8") (pintype "passive"))
      (node (ref "USB") (pin "5") (pinfunction "5_5") (pintype "passive"))
      (node (ref "X1") (pin "GND") (pinfunction "GND_GND") (pintype "bidirectional"))
    )
    (net (code "32") (name "Net-(CV_A-3)") (class "Default")
      (node (ref "CV_A") (pin "P$2") (pinfunction "3_P$2") (pintype "passive"))
      (node (ref "POT1") (pin "3") (pinfunction "3_3") (pintype "bidirectional"))
    )
    (net (code "33") (name "Net-(CV_B-3)") (class "Default")
      (node (ref "CV_B") (pin "P$2") (pinfunction "3_P$2") (pintype "passive"))
      (node (ref "POT2") (pin "3") (pinfunction "3_3") (pintype "bidirectional"))
    )
    (net (code "34") (name "Net-(CV_C-3)") (class "Default")
      (node (ref "CV_C") (pin "P$2") (pinfunction "3_P$2") (pintype "passive"))
      (node (ref "POT3") (pin "3") (pinfunction "3_3") (pintype "bidirectional"))
    )
    (net (code "35") (name "Net-(CV_D-3)") (class "Default")
      (node (ref "CV_D") (pin "P$2") (pinfunction "3_P$2") (pintype "passive"))
      (node (ref "POT4") (pin "3") (pinfunction "3_3") (pintype "bidirectional"))
    )
    (net (code "36") (name "Net-(D200-C1A2)") (class "Default")
      (node (ref "D200") (pin "3") (pinfunction "C1A2_3") (pintype "passive"))
      (node (ref "R200") (pin "2") (pinfunction "2_2") (pintype "passive"))
      (node (ref "R202") (pin "1") (pinfunction "1_1") (pintype "passive"))
    )
    (net (code "37") (name "Net-(D500-C1A2)") (class "Default")
      (node (ref "D500") (pin "3") (pinfunction "C1A2_3") (pintype "passive"))
      (node (ref "R504") (pin "1") (pinfunction "1_1") (pintype "passive"))
      (node (ref "R505") (pin "2") (pinfunction "2_2") (pintype "passive"))
    )
    (net (code "38") (name "Net-(D600-C1A2)") (class "Default")
      (node (ref "D600") (pin "3") (pinfunction "C1A2_3") (pintype "passive"))
      (node (ref "R604") (pin "1") (pinfunction "1_1") (pintype "passive"))
      (node (ref "R605") (pin "2") (pinfunction "2_2") (pintype "passive"))
    )
    (net (code "39") (name "Net-(D700-C1A2)") (class "Default")
      (node (ref "D700") (pin "3") (pinfunction "C1A2_3") (pintype "passive"))
      (node (ref "R704") (pin "1") (pinfunction "1_1") (pintype "passive"))
      (node (ref "R705") (pin "2") (pinfunction "2_2") (pintype "passive"))
    )
    (net (code "40") (name "Net-(D800-C1A2)") (class "Default")
      (node (ref "D800") (pin "3") (pinfunction "C1A2_3") (pintype "passive"))
      (node (ref "R804") (pin "1") (pinfunction "1_1") (pintype "passive"))
      (node (ref "R805") (pin "2") (pinfunction "2_2") (pintype "passive"))
    )
    (net (code "41") (name "Net-(EXP-3)") (class "Default")
      (node (ref "EXP") (pin "P$2") (pinfunction "3_P$2") (pintype "passive"))
      (node (ref "R200") (pin "1") (pinfunction "1_1") (pintype "passive"))
    )
    (net (code "42") (name "Net-(F1-1)") (class "Default")
      (node (ref "F1") (pin "P$1") (pinfunction "1_P$1") (pintype "bidirectional"))
      (node (ref "U$2") (pin "11") (pinfunction "11_11") (pintype "passive"))
      (node (ref "U$2") (pin "12") (pinfunction "12_12") (pintype "passive"))
    )
    (net (code "43") (name "Net-(F2-1)") (class "Default")
      (node (ref "F2") (pin "P$1") (pinfunction "1_P$1") (pintype "bidirectional"))
      (node (ref "U$2") (pin "10") (pinfunction "10_10") (pintype "passive"))
      (node (ref "U$2") (pin "9") (pinfunction "9_9") (pintype "passive"))
    )
    (net (code "44") (name "Net-(F3-2)") (class "Default")
      (node (ref "F3") (pin "P$2") (pinfunction "2_P$2") (pintype "bidirectional"))
      (node (ref "U$2") (pin "1") (pinfunction "1_1") (pintype "passive"))
      (node (ref "U$2") (pin "2") (pinfunction "2_2") (pintype "passive"))
    )
    (net (code "45") (name "Net-(IC1A--IN)") (class "Default")
      (node (ref "IC1") (pin "2") (pinfunction "-IN_2") (pintype "input"))
      (node (ref "R300") (pin "1") (pinfunction "1_1") (pintype "passive"))
      (node (ref "R302") (pin "2") (pinfunction "2_2") (pintype "passive"))
    )
    (net (code "46") (name "Net-(IC1A-OUT)") (class "Default")
      (node (ref "IC1") (pin "1") (pinfunction "OUT_1") (pintype "output"))
      (node (ref "R302") (pin "1") (pinfunction "1_1") (pintype "passive"))
      (node (ref "R304") (pin "2") (pinfunction "2_2") (pintype "passive"))
    )
    (net (code "47") (name "Net-(IC1B--IN)") (class "Default")
      (node (ref "IC1") (pin "6") (pinfunction "-IN_6") (pintype "input"))
      (node (ref "R304") (pin "1") (pinfunction "1_1") (pintype "passive"))
      (node (ref "R306") (pin "1") (pinfunction "1_1") (pintype "passive"))
      (node (ref "R308") (pin "2") (pinfunction "2_2") (pintype "passive"))
    )
    (net (code "48") (name "Net-(IC1B-OUT)") (class "Default")
      (node (ref "IC1") (pin "7") (pinfunction "OUT_7") (pintype "output"))
      (node (ref "R308") (pin "1") (pinfunction "1_1") (pintype "passive"))
      (node (ref "R310") (pin "2") (pinfunction "2_2") (pintype "passive"))
    )
    (net (code "49") (name "Net-(IC1C--IN)") (class "Default")
      (node (ref "IC1") (pin "9") (pinfunction "-IN_9") (pintype "input"))
      (node (ref "R301") (pin "1") (pinfunction "1_1") (pintype "passive"))
      (node (ref "R303") (pin "2") (pinfunction "2_2") (pintype "passive"))
    )
    (net (code "50") (name "Net-(IC1C-OUT)") (class "Default")
      (node (ref "IC1") (pin "8") (pinfunction "OUT_8") (pintype "output"))
      (node (ref "R303") (pin "1") (pinfunction "1_1") (pintype "passive"))
      (node (ref "R305") (pin "2") (pinfunction "2_2") (pintype "passive"))
    )
    (net (code "51") (name "Net-(IC1D--IN)") (class "Default")
      (node (ref "IC1") (pin "13") (pinfunction "-IN_13") (pintype "input"))
      (node (ref "R305") (pin "1") (pinfunction "1_1") (pintype "passive"))
      (node (ref "R307") (pin "1") (pinfunction "1_1") (pintype "passive"))
      (node (ref "R309") (pin "2") (pinfunction "2_2") (pintype "passive"))
    )
    (net (code "52") (name "Net-(IC1D-OUT)") (class "Default")
      (node (ref "IC1") (pin "14") (pinfunction "OUT_14") (pintype "output"))
      (node (ref "R309") (pin "1") (pinfunction "1_1") (pintype "passive"))
      (node (ref "R311") (pin "2") (pinfunction "2_2") (pintype "passive"))
    )
    (net (code "53") (name "Net-(IC2A--IN)") (class "Default")
      (node (ref "IC2") (pin "2") (pinfunction "-IN_2") (pintype "input"))
      (node (ref "R500") (pin "2") (pinfunction "2_2") (pintype "passive"))
      (node (ref "R501") (pin "2") (pinfunction "2_2") (pintype "passive"))
      (node (ref "R502") (pin "2") (pinfunction "2_2") (pintype "passive"))
      (node (ref "R503") (pin "1") (pinfunction "1_1") (pintype "passive"))
    )
    (net (code "54") (name "Net-(IC2A-OUT)") (class "Default")
      (node (ref "IC2") (pin "1") (pinfunction "OUT_1") (pintype "output"))
      (node (ref "R503") (pin "2") (pinfunction "2_2") (pintype "passive"))
      (node (ref "R504") (pin "2") (pinfunction "2_2") (pintype "passive"))
    )
    (net (code "55") (name "Net-(IC2B--IN)") (class "Default")
      (node (ref "IC2") (pin "6") (pinfunction "-IN_6") (pintype "input"))
      (node (ref "R600") (pin "2") (pinfunction "2_2") (pintype "passive"))
      (node (ref "R601") (pin "2") (pinfunction "2_2") (pintype "passive"))
      (node (ref "R602") (pin "2") (pinfunction "2_2") (pintype "passive"))
      (node (ref "R603") (pin "1") (pinfunction "1_1") (pintype "passive"))
    )
    (net (code "56") (name "Net-(IC2B-OUT)") (class "Default")
      (node (ref "IC2") (pin "7") (pinfunction "OUT_7") (pintype "output"))
      (node (ref "R603") (pin "2") (pinfunction "2_2") (pintype "passive"))
      (node (ref "R604") (pin "2") (pinfunction "2_2") (pintype "passive"))
    )
    (net (code "57") (name "Net-(IC2C--IN)") (class "Default")
      (node (ref "IC2") (pin "9") (pinfunction "-IN_9") (pintype "input"))
      (node (ref "R700") (pin "2") (pinfunction "2_2") (pintype "passive"))
      (node (ref "R701") (pin "2") (pinfunction "2_2") (pintype "passive"))
      (node (ref "R702") (pin "2") (pinfunction "2_2") (pintype "passive"))
      (node (ref "R703") (pin "1") (pinfunction "1_1") (pintype "passive"))
    )
    (net (code "58") (name "Net-(IC2C-OUT)") (class "Default")
      (node (ref "IC2") (pin "8") (pinfunction "OUT_8") (pintype "output"))
      (node (ref "R703") (pin "2") (pinfunction "2_2") (pintype "passive"))
      (node (ref "R704") (pin "2") (pinfunction "2_2") (pintype "passive"))
    )
    (net (code "59") (name "Net-(IC2D--IN)") (class "Default")
      (node (ref "IC2") (pin "13") (pinfunction "-IN_13") (pintype "input"))
      (node (ref "R800") (pin "2") (pinfunction "2_2") (pintype "passive"))
      (node (ref "R801") (pin "2") (pinfunction "2_2") (pintype "passive"))
      (node (ref "R802") (pin "2") (pinfunction "2_2") (pintype "passive"))
      (node (ref "R803") (pin "1") (pinfunction "1_1") (pintype "passive"))
    )
    (net (code "60") (name "Net-(IC2D-OUT)") (class "Default")
      (node (ref "IC2") (pin "14") (pinfunction "OUT_14") (pintype "output"))
      (node (ref "R803") (pin "2") (pinfunction "2_2") (pintype "passive"))
      (node (ref "R804") (pin "2") (pinfunction "2_2") (pintype "passive"))
    )
    (net (code "61") (name "Net-(IC3A--IN)") (class "Default")
      (node (ref "IC3") (pin "2") (pinfunction "-IN_2") (pintype "input"))
      (node (ref "R400") (pin "2") (pinfunction "2_2") (pintype "passive"))
      (node (ref "R402") (pin "2") (pinfunction "2_2") (pintype "passive"))
      (node (ref "R404") (pin "1") (pinfunction "1_1") (pintype "passive"))
    )
    (net (code "62") (name "Net-(IC3A-OUT)") (class "Default")
      (node (ref "IC3") (pin "1") (pinfunction "OUT_1") (pintype "output"))
      (node (ref "R404") (pin "2") (pinfunction "2_2") (pintype "passive"))
      (node (ref "R406") (pin "1") (pinfunction "1_1") (pintype "passive"))
    )
    (net (code "63") (name "Net-(IC3B--IN)") (class "Default")
      (node (ref "IC3") (pin "6") (pinfunction "-IN_6") (pintype "input"))
      (node (ref "R401") (pin "2") (pinfunction "2_2") (pintype "passive"))
      (node (ref "R403") (pin "2") (pinfunction "2_2") (pintype "passive"))
      (node (ref "R405") (pin "1") (pinfunction "1_1") (pintype "passive"))
    )
    (net (code "64") (name "Net-(IC3B-OUT)") (class "Default")
      (node (ref "IC3") (pin "7") (pinfunction "OUT_7") (pintype "output"))
      (node (ref "R405") (pin "2") (pinfunction "2_2") (pintype "passive"))
      (node (ref "R407") (pin "1") (pinfunction "1_1") (pintype "passive"))
    )
    (net (code "65") (name "Net-(IN_D-3)") (class "Default")
      (node (ref "IN_D") (pin "P$2") (pinfunction "3_P$2") (pintype "passive"))
      (node (ref "R904") (pin "1") (pinfunction "1_1") (pintype "passive"))
    )
    (net (code "66") (name "Net-(OUT_D-3)") (class "Default")
      (node (ref "OUT_D") (pin "P$2") (pinfunction "3_P$2") (pintype "passive"))
      (node (ref "R902") (pin "1") (pinfunction "1_1") (pintype "passive"))
      (node (ref "R903") (pin "2") (pinfunction "2_2") (pintype "passive"))
    )
    (net (code "67") (name "Net-(POT1-Pad2)") (class "Default")
      (node (ref "POT1") (pin "2") (pinfunction "2_2") (pintype "bidirectional"))
      (node (ref "R501") (pin "1") (pinfunction "1_1") (pintype "passive"))
    )
    (net (code "68") (name "Net-(POT2-Pad2)") (class "Default")
      (node (ref "POT2") (pin "2") (pinfunction "2_2") (pintype "bidirectional"))
      (node (ref "R601") (pin "1") (pinfunction "1_1") (pintype "passive"))
    )
    (net (code "69") (name "Net-(POT3-Pad2)") (class "Default")
      (node (ref "POT3") (pin "2") (pinfunction "2_2") (pintype "bidirectional"))
      (node (ref "R701") (pin "1") (pinfunction "1_1") (pintype "passive"))
    )
    (net (code "70") (name "Net-(POT4-Pad2)") (class "Default")
      (node (ref "POT4") (pin "2") (pinfunction "2_2") (pintype "bidirectional"))
      (node (ref "R801") (pin "1") (pinfunction "1_1") (pintype "passive"))
    )
    (net (code "71") (name "Net-(POT5-Pad2)") (class "Default")
      (node (ref "POT5") (pin "2") (pinfunction "2_2") (pintype "bidirectional"))
      (node (ref "R500") (pin "1") (pinfunction "1_1") (pintype "passive"))
    )
    (net (code "72") (name "Net-(POT6-Pad2)") (class "Default")
      (node (ref "POT6") (pin "2") (pinfunction "2_2") (pintype "bidirectional"))
      (node (ref "R600") (pin "1") (pinfunction "1_1") (pintype "passive"))
    )
    (net (code "73") (name "Net-(POT7-Pad2)") (class "Default")
      (node (ref "POT7") (pin "2") (pinfunction "2_2") (pintype "bidirectional"))
      (node (ref "R700") (pin "1") (pinfunction "1_1") (pintype "passive"))
    )
    (net (code "74") (name "Net-(POT8-Pad2)") (class "Default")
      (node (ref "POT8") (pin "2") (pinfunction "2_2") (pintype "bidirectional"))
      (node (ref "R800") (pin "1") (pinfunction "1_1") (pintype "passive"))
    )
    (net (code "75") (name "Net-(Q900-B)") (class "Default")
      (node (ref "Q900") (pin "1") (pinfunction "B_1") (pintype "passive"))
      (node (ref "R900") (pin "2") (pinfunction "2_2") (pintype "passive"))
    )
    (net (code "76") (name "Net-(Q900-C)") (class "Default")
      (node (ref "Q900") (pin "3") (pinfunction "C_3") (pintype "passive"))
      (node (ref "R901") (pin "1") (pinfunction "1_1") (pintype "passive"))
      (node (ref "R902") (pin "2") (pinfunction "2_2") (pintype "passive"))
    )
    (net (code "77") (name "Net-(Q901-B)") (class "Default")
      (node (ref "Q901") (pin "1") (pinfunction "B_1") (pintype "passive"))
      (node (ref "R904") (pin "2") (pinfunction "2_2") (pintype "passive"))
      (node (ref "R905") (pin "2") (pinfunction "2_2") (pintype "passive"))
    )
    (net (code "78") (name "Net-(R101-Pad2)") (class "Default")
      (node (ref "R101") (pin "2") (pinfunction "2_2") (pintype "passive"))
      (node (ref "X1") (pin "D+") (pinfunction "D+_D+") (pintype "bidirectional"))
    )
    (net (code "79") (name "Net-(R102-Pad2)") (class "Default")
      (node (ref "R102") (pin "2") (pinfunction "2_2") (pintype "passive"))
      (node (ref "X1") (pin "D-") (pinfunction "D-_D-") (pintype "bidirectional"))
    )
    (net (code "80") (name "Net-(R103-Pad2)") (class "Default")
      (node (ref "R103") (pin "2") (pinfunction "2_2") (pintype "passive"))
      (node (ref "X1") (pin "VBUS") (pinfunction "VBUS_VBUS") (pintype "bidirectional"))
    )
    (net (code "81") (name "Net-(U$1-LED_R+)") (class "Default")
      (node (ref "R100") (pin "1") (pinfunction "1_1") (pintype "passive"))
      (node (ref "U$1") (pin "+3") (pinfunction "LED_R+_+3") (pintype "input"))
    )
    (net (code "82") (name "VCC{slash}2") (class "Default")
      (node (ref "VMID") (pin "1") (pinfunction "1_1") (pintype "passive"))
    )
    (net (code "83") (name "unconnected-(OUT_D-4-PadP$1)") (class "Default")
      (node (ref "OUT_D") (pin "P$1") (pinfunction "4_P$1") (pintype "passive"))
    )
    (net (code "84") (name "unconnected-(OUT_L-4-PadP$1)") (class "Default")
      (node (ref "OUT_L") (pin "P$1") (pinfunction "4_P$1") (pintype "passive"))
    )
    (net (code "85") (name "unconnected-(OUT_R-4-PadP$1)") (class "Default")
      (node (ref "OUT_R") (pin "P$1") (pinfunction "4_P$1") (pintype "passive"))
    )
    (net (code "86") (name "unconnected-(U$2-Pad13)") (class "Default")
      (node (ref "U$2") (pin "13") (pinfunction "13_13") (pintype "passive"))
    )
    (net (code "87") (name "unconnected-(U$2-Pad14)") (class "Default")
      (node (ref "U$2") (pin "14") (pinfunction "14_14") (pintype "passive"))
    )
    (net (code "88") (name "unconnected-(U$2-Pad15)") (class "Default")
      (node (ref "U$2") (pin "15") (pinfunction "15_15") (pintype "passive"))
    )
    (net (code "89") (name "unconnected-(U$2-Pad16)") (class "Default")
      (node (ref "U$2") (pin "16") (pinfunction "16_16") (pintype "passive"))
    )
  )
)
